# ECE477_schematic.net
KiCad netlist of a schematic drawn in EAGLE
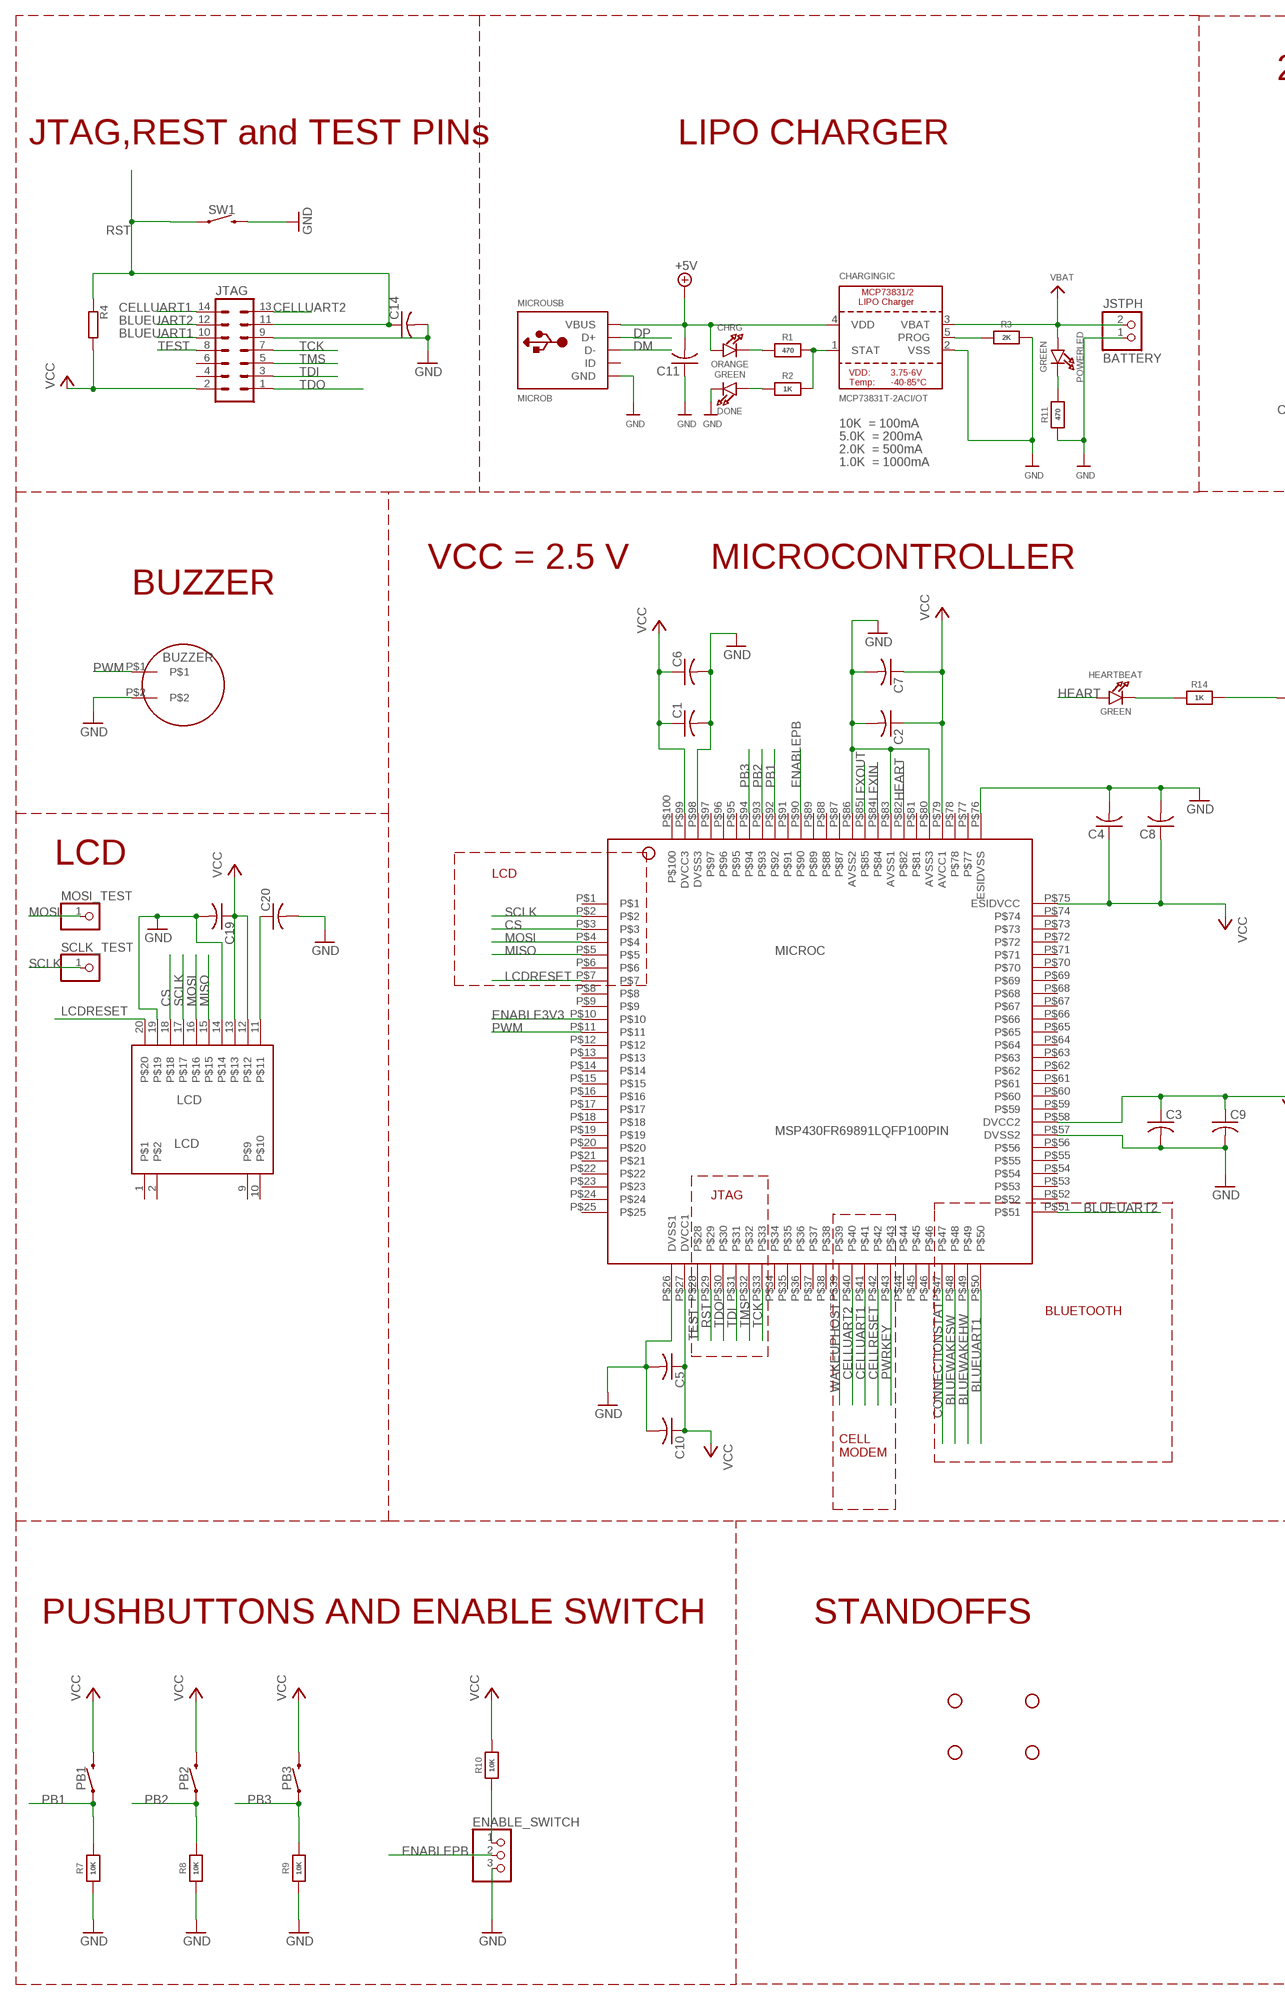
[diagram p0: schematic, sheet 1, part 1 of 2]
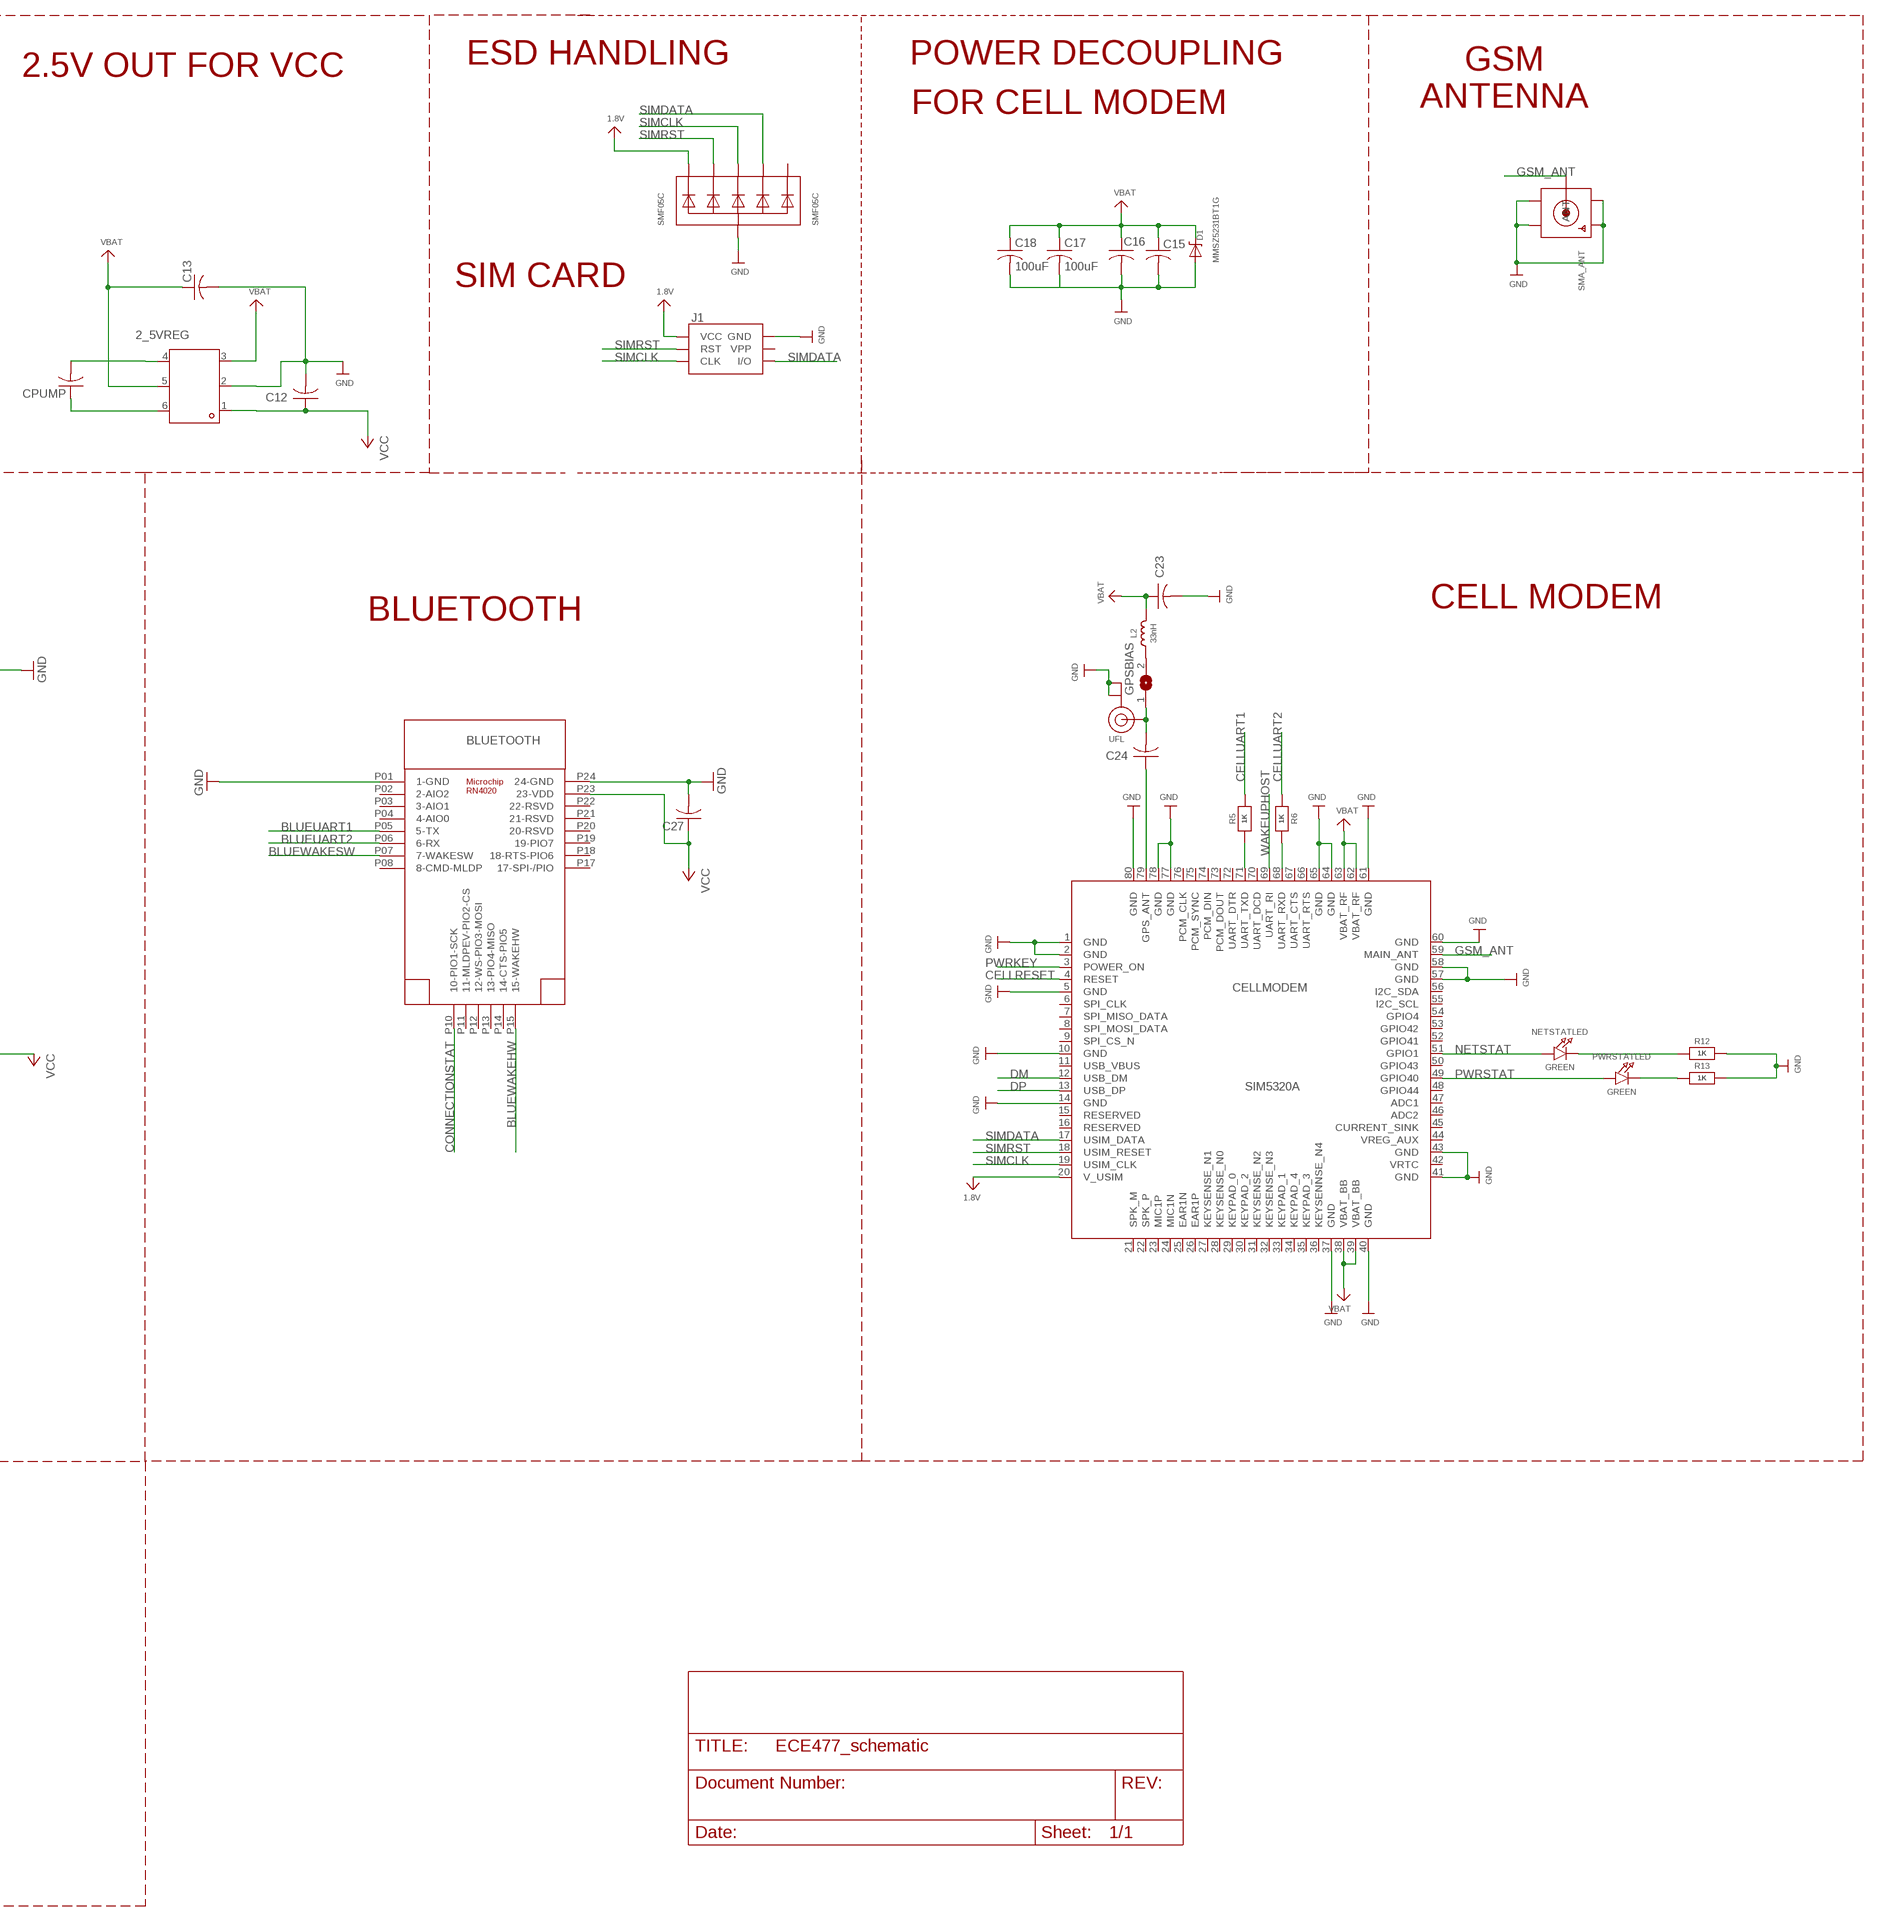
[diagram p1: schematic, sheet 1, part 2 of 2]

(export (version "E")
  (design (tool "Eeschema 10.0.6"))
  (components
    (comp (ref "2_5VREG")
      (value "2_5VREG")
      (footprint "eagle-import:REG710NASOC6")
      (libsource (lib "eagle-import") (part "2_5VREG"))
    )
    (comp (ref "BATTERY")
      (value "JSTPH")
      (footprint "eagle-import:JSTPH2")
      (libsource (lib "eagle-import") (part "JST_2PIN"))
    )
    (comp (ref "BLUETOOTH")
      (value "RN4020")
      (footprint "eagle-import:RN4020SMD")
      (libsource (lib "eagle-import") (part "RN4020"))
    )
    (comp (ref "BUZZER")
      (value "BUZZER")
      (footprint "eagle-import:BUZZERTHROUGHHOLE")
      (libsource (lib "eagle-import") (part "BUZZER"))
    )
    (comp (ref "C1")
      (value "C-USC1206")
      (footprint "eagle-import:C1206")
      (libsource (lib "eagle-import") (part "rcl_334_C-USC1206"))
    )
    (comp (ref "C2")
      (value "C-USC1206")
      (footprint "eagle-import:C1206")
      (libsource (lib "eagle-import") (part "rcl_334_C-USC1206"))
    )
    (comp (ref "C3")
      (value "C-USC1206")
      (footprint "eagle-import:C1206")
      (libsource (lib "eagle-import") (part "rcl_334_C-USC1206"))
    )
    (comp (ref "C4")
      (value "C-USC1206")
      (footprint "eagle-import:C1206")
      (libsource (lib "eagle-import") (part "rcl_334_C-USC1206"))
    )
    (comp (ref "C5")
      (value "C-USC1206")
      (footprint "eagle-import:C1206")
      (libsource (lib "eagle-import") (part "rcl_334_C-USC1206"))
    )
    (comp (ref "C6")
      (value "C-USC1206")
      (footprint "eagle-import:C1206")
      (libsource (lib "eagle-import") (part "rcl_334_C-USC1206"))
    )
    (comp (ref "C7")
      (value "C-USC1206")
      (footprint "eagle-import:C1206")
      (libsource (lib "eagle-import") (part "rcl_334_C-USC1206"))
    )
    (comp (ref "C8")
      (value "C-USC1206")
      (footprint "eagle-import:C1206")
      (libsource (lib "eagle-import") (part "rcl_334_C-USC1206"))
    )
    (comp (ref "C9")
      (value "C-USC1206")
      (footprint "eagle-import:C1206")
      (libsource (lib "eagle-import") (part "rcl_334_C-USC1206"))
    )
    (comp (ref "C10")
      (value "C-USC1206")
      (footprint "eagle-import:C1206")
      (libsource (lib "eagle-import") (part "rcl_334_C-USC1206"))
    )
    (comp (ref "C11")
      (value "C-USC1206")
      (footprint "eagle-import:C1206")
      (libsource (lib "eagle-import") (part "rcl_334_C-USC1206"))
    )
    (comp (ref "C12")
      (value "C-USC1206")
      (footprint "eagle-import:C1206")
      (libsource (lib "eagle-import") (part "rcl_334_C-USC1206"))
    )
    (comp (ref "C13")
      (value "C-USC1206")
      (footprint "eagle-import:C1206")
      (libsource (lib "eagle-import") (part "rcl_334_C-USC1206"))
    )
    (comp (ref "C14")
      (value "C-USC1206")
      (footprint "eagle-import:C1206")
      (libsource (lib "eagle-import") (part "rcl_334_C-USC1206"))
    )
    (comp (ref "C15")
      (value "C-USC1206")
      (footprint "eagle-import:C1206")
      (libsource (lib "eagle-import") (part "rcl_334_C-USC1206"))
    )
    (comp (ref "C16")
      (value "C-USC1206")
      (footprint "eagle-import:C1206")
      (libsource (lib "eagle-import") (part "rcl_334_C-USC1206"))
    )
    (comp (ref "C17")
      (value "100uF")
      (footprint "eagle-import:C1210")
      (libsource (lib "eagle-import") (part "C-USC1210"))
    )
    (comp (ref "C18")
      (value "100uF")
      (footprint "eagle-import:C1210")
      (libsource (lib "eagle-import") (part "C-USC1210"))
    )
    (comp (ref "C19")
      (value "C-USC1206")
      (footprint "eagle-import:C1206")
      (libsource (lib "eagle-import") (part "rcl_334_C-USC1206"))
    )
    (comp (ref "C20")
      (value "C-USC1206")
      (footprint "eagle-import:C1206")
      (libsource (lib "eagle-import") (part "rcl_334_C-USC1206"))
    )
    (comp (ref "C23")
      (value "C-USC1206")
      (footprint "eagle-import:C1206")
      (libsource (lib "eagle-import") (part "rcl_334_C-USC1206"))
    )
    (comp (ref "C24")
      (value "C-USC1206")
      (footprint "eagle-import:C1206")
      (libsource (lib "eagle-import") (part "rcl_334_C-USC1206"))
    )
    (comp (ref "C27")
      (value "C-USC1206")
      (footprint "eagle-import:C1206")
      (libsource (lib "eagle-import") (part "rcl_334_C-USC1206"))
    )
    (comp (ref "CELLMODEM")
      (value "SIM5320A")
      (footprint "eagle-import:MICROBUILDER_SIM5320")
      (libsource (lib "eagle-import") (part "SIM5320"))
    )
    (comp (ref "CHARGINGIC")
      (value "MCP73831T-2ACI/OT")
      (footprint "eagle-import:SOT23-5")
      (libsource (lib "eagle-import") (part "MCP73831/2"))
    )
    (comp (ref "CHRG")
      (value "ORANGE")
      (footprint "eagle-import:CHIPLED_0805_NOOUTLINE")
      (libsource (lib "eagle-import") (part "LED0805_NOOUTLINE"))
    )
    (comp (ref "CPUMP")
      (value "C-USC1206")
      (footprint "eagle-import:C1206")
      (libsource (lib "eagle-import") (part "rcl_334_C-USC1206"))
    )
    (comp (ref "D1")
      (value "MMSZ5231BT1G")
      (footprint "eagle-import:SOD-123")
      (libsource (lib "eagle-import") (part "DIODE-ZENERSOD123"))
    )
    (comp (ref "DONE")
      (value "GREEN")
      (footprint "eagle-import:CHIPLED_0805_NOOUTLINE")
      (libsource (lib "eagle-import") (part "LED0805_NOOUTLINE"))
    )
    (comp (ref "ENABLE_SWITCH")
      (value "PINHD-1X3")
      (footprint "eagle-import:1X03")
      (libsource (lib "eagle-import") (part "PINHD-1X3"))
    )
    (comp (ref "GPSBIAS")
      (value "SOLDERJUMPER")
      (footprint "eagle-import:SOLDERJUMPER_ARROW_NOPASTE")
      (libsource (lib "eagle-import") (part "SOLDERJUMPER"))
    )
    (comp (ref "H1")
      (value "STAND-OFF")
      (footprint "eagle-import:STAND-OFF")
      (libsource (lib "eagle-import") (part "STAND-OFF"))
    )
    (comp (ref "H2")
      (value "STAND-OFF")
      (footprint "eagle-import:STAND-OFF")
      (libsource (lib "eagle-import") (part "STAND-OFF"))
    )
    (comp (ref "H3")
      (value "STAND-OFF")
      (footprint "eagle-import:STAND-OFF")
      (libsource (lib "eagle-import") (part "STAND-OFF"))
    )
    (comp (ref "H4")
      (value "STAND-OFF")
      (footprint "eagle-import:STAND-OFF")
      (libsource (lib "eagle-import") (part "STAND-OFF"))
    )
    (comp (ref "HEARTBEAT")
      (value "GREEN")
      (footprint "eagle-import:CHIPLED_0805_NOOUTLINE")
      (libsource (lib "eagle-import") (part "LED0805_NOOUTLINE"))
    )
    (comp (ref "J1")
      (value "SIMHOLDERSIM")
      (footprint "eagle-import:SIMHOLDER")
      (libsource (lib "eagle-import") (part "SIMHOLDERSIM"))
    )
    (comp (ref "JTAG")
      (value "CON-ML_ML14")
      (footprint "eagle-import:CON-ML_ML14")
      (libsource (lib "eagle-import") (part "CON-ML_ML14"))
    )
    (comp (ref "L2")
      (value "33nH")
      (footprint "eagle-import:_0805MP")
      (libsource (lib "eagle-import") (part "INDUCTOR_0805MP"))
    )
    (comp (ref "LCD")
      (value "LCD")
      (footprint "eagle-import:LCDTHROUGHHOLE")
      (libsource (lib "eagle-import") (part "LCD"))
    )
    (comp (ref "MICROC")
      (value "MSP430FR69891LQFP100PIN")
      (footprint "eagle-import:MSP430FR69891")
      (libsource (lib "eagle-import") (part "MSP430FR69891LQFP100PIN"))
    )
    (comp (ref "MICROUSB")
      (value "MICROB")
      (footprint "eagle-import:ZX62DB5PA8(30)")
      (libsource (lib "eagle-import") (part "MICROB"))
    )
    (comp (ref "MOSI_TEST")
      (value "PINHD-1X1")
      (footprint "eagle-import:1X01")
      (libsource (lib "eagle-import") (part "PINHD-1X1"))
    )
    (comp (ref "NETSTATLED")
      (value "GREEN")
      (footprint "eagle-import:CHIPLED_0805_NOOUTLINE")
      (libsource (lib "eagle-import") (part "LED0805_NOOUTLINE"))
    )
    (comp (ref "PB1")
      (value "MOMENTARY-SWITCH-SPST-PTH-6.0MM")
      (footprint "eagle-import:TACTILE_SWITCH_PTH_6.0MM")
      (libsource (lib "eagle-import") (part "MOMENTARY-SWITCH-SPST-PTH-6.0MM"))
    )
    (comp (ref "PB2")
      (value "MOMENTARY-SWITCH-SPST-PTH-6.0MM")
      (footprint "eagle-import:TACTILE_SWITCH_PTH_6.0MM")
      (libsource (lib "eagle-import") (part "MOMENTARY-SWITCH-SPST-PTH-6.0MM"))
    )
    (comp (ref "PB3")
      (value "MOMENTARY-SWITCH-SPST-PTH-6.0MM")
      (footprint "eagle-import:TACTILE_SWITCH_PTH_6.0MM")
      (libsource (lib "eagle-import") (part "MOMENTARY-SWITCH-SPST-PTH-6.0MM"))
    )
    (comp (ref "POWERLED")
      (value "GREEN")
      (footprint "eagle-import:CHIPLED_0805_NOOUTLINE")
      (libsource (lib "eagle-import") (part "LED0805_NOOUTLINE"))
    )
    (comp (ref "PWRSTATLED")
      (value "GREEN")
      (footprint "eagle-import:CHIPLED_0805_NOOUTLINE")
      (libsource (lib "eagle-import") (part "LED0805_NOOUTLINE"))
    )
    (comp (ref "R1")
      (value "470")
      (footprint "eagle-import:0805-NO")
      (libsource (lib "eagle-import") (part "RESISTOR0805_NOOUTLINE"))
    )
    (comp (ref "R2")
      (value "1K")
      (footprint "eagle-import:0805-NO")
      (libsource (lib "eagle-import") (part "RESISTOR0805_NOOUTLINE"))
    )
    (comp (ref "R3")
      (value "2K")
      (footprint "eagle-import:0805-NO")
      (libsource (lib "eagle-import") (part "RESISTOR0805_NOOUTLINE"))
    )
    (comp (ref "R4")
      (value "SMD_R_0805")
      (footprint "eagle-import:SMD_0805")
      (libsource (lib "eagle-import") (part "SMD_R_0805"))
    )
    (comp (ref "R5")
      (value "1K")
      (footprint "eagle-import:0805-NO")
      (libsource (lib "eagle-import") (part "RESISTOR0805_NOOUTLINE"))
    )
    (comp (ref "R6")
      (value "1K")
      (footprint "eagle-import:0805-NO")
      (libsource (lib "eagle-import") (part "RESISTOR0805_NOOUTLINE"))
    )
    (comp (ref "R7")
      (value "10K")
      (footprint "eagle-import:0805-NO")
      (libsource (lib "eagle-import") (part "RESISTOR0805_NOOUTLINE"))
    )
    (comp (ref "R8")
      (value "10K")
      (footprint "eagle-import:0805-NO")
      (libsource (lib "eagle-import") (part "RESISTOR0805_NOOUTLINE"))
    )
    (comp (ref "R9")
      (value "10K")
      (footprint "eagle-import:0805-NO")
      (libsource (lib "eagle-import") (part "RESISTOR0805_NOOUTLINE"))
    )
    (comp (ref "R10")
      (value "10K")
      (footprint "eagle-import:0805-NO")
      (libsource (lib "eagle-import") (part "RESISTOR0805_NOOUTLINE"))
    )
    (comp (ref "R11")
      (value "470")
      (footprint "eagle-import:0805-NO")
      (libsource (lib "eagle-import") (part "RESISTOR0805_NOOUTLINE"))
    )
    (comp (ref "R12")
      (value "1K")
      (footprint "eagle-import:0805-NO")
      (libsource (lib "eagle-import") (part "RESISTOR0805_NOOUTLINE"))
    )
    (comp (ref "R13")
      (value "1K")
      (footprint "eagle-import:0805-NO")
      (libsource (lib "eagle-import") (part "RESISTOR0805_NOOUTLINE"))
    )
    (comp (ref "R14")
      (value "1K")
      (footprint "eagle-import:0805-NO")
      (libsource (lib "eagle-import") (part "RESISTOR0805_NOOUTLINE"))
    )
    (comp (ref "SCLK_TEST")
      (value "PINHD-1X1")
      (footprint "eagle-import:1X01")
      (libsource (lib "eagle-import") (part "PINHD-1X1"))
    )
    (comp (ref "SMA_ANT")
      (value "MICROBUILDER_SMACONNECTOR_EDGE")
      (footprint "eagle-import:MICROBUILDER_SMA_EDGELAUNCH")
      (libsource (lib "eagle-import") (part "MICROBUILDER_SMACONNECTOR_EDGE"))
    )
    (comp (ref "SMF05C")
      (value "SMF05C")
      (footprint "eagle-import:SOT363")
      (libsource (lib "eagle-import") (part "TVSARRAY_5LANE"))
    )
    (comp (ref "SW1")
      (value "MOMENTARY-SWITCH-SPST-PTH-6.0MM")
      (footprint "eagle-import:TACTILE_SWITCH_PTH_6.0MM")
      (libsource (lib "eagle-import") (part "MOMENTARY-SWITCH-SPST-PTH-6.0MM"))
    )
    (comp (ref "UFL")
      (value "MICROBUILDER_ANTENNA_U.FL")
      (footprint "eagle-import:MICROBUILDER_U.FL")
      (libsource (lib "eagle-import") (part "MICROBUILDER_ANTENNA_U.FL"))
    )
  )
  (nets
    (net (code "1") (name "+5V") (class "Default")
      (node (ref "C11") (pin "2") (pinfunction "2_2") (pintype "passive"))
      (node (ref "CHARGINGIC") (pin "4") (pinfunction "VDD_4") (pintype "power_in"))
      (node (ref "CHRG") (pin "A") (pinfunction "A_A") (pintype "passive"))
      (node (ref "MICROUSB") (pin "+5V") (pinfunction "VBUS_+5V") (pintype "power_in"))
    )
    (net (code "2") (name "/BLUEUART1") (class "Default")
      (node (ref "BLUETOOTH") (pin "P05") (pinfunction "5-TX_P05") (pintype "bidirectional"))
      (node (ref "JTAG") (pin "10") (pinfunction "10_10") (pintype "passive"))
      (node (ref "MICROC") (pin "P$50") (pinfunction "P$50_P$50") (pintype "bidirectional"))
    )
    (net (code "3") (name "/BLUEUART2") (class "Default")
      (node (ref "BLUETOOTH") (pin "P06") (pinfunction "6-RX_P06") (pintype "bidirectional"))
      (node (ref "JTAG") (pin "12") (pinfunction "12_12") (pintype "passive"))
      (node (ref "MICROC") (pin "P$51") (pinfunction "P$51_P$51") (pintype "bidirectional"))
    )
    (net (code "4") (name "/BLUEWAKEHW") (class "Default")
      (node (ref "BLUETOOTH") (pin "P15") (pinfunction "15-WAKEHW_P15") (pintype "bidirectional"))
      (node (ref "MICROC") (pin "P$49") (pinfunction "P$49_P$49") (pintype "bidirectional"))
    )
    (net (code "5") (name "/BLUEWAKESW") (class "Default")
      (node (ref "BLUETOOTH") (pin "P07") (pinfunction "7-WAKESW_P07") (pintype "bidirectional"))
      (node (ref "MICROC") (pin "P$48") (pinfunction "P$48_P$48") (pintype "bidirectional"))
    )
    (net (code "6") (name "/CELLRESET") (class "Default")
      (node (ref "CELLMODEM") (pin "4") (pinfunction "RESET_4") (pintype "bidirectional"))
      (node (ref "MICROC") (pin "P$42") (pinfunction "P$42_P$42") (pintype "bidirectional"))
    )
    (net (code "7") (name "/CELLUART1") (class "Default")
      (node (ref "JTAG") (pin "14") (pinfunction "14_14") (pintype "passive"))
      (node (ref "MICROC") (pin "P$41") (pinfunction "P$41_P$41") (pintype "bidirectional"))
      (node (ref "R5") (pin "2") (pinfunction "2_2") (pintype "passive"))
    )
    (net (code "8") (name "/CELLUART2") (class "Default")
      (node (ref "JTAG") (pin "13") (pinfunction "13_13") (pintype "passive"))
      (node (ref "MICROC") (pin "P$40") (pinfunction "P$40_P$40") (pintype "bidirectional"))
      (node (ref "R6") (pin "2") (pinfunction "2_2") (pintype "passive"))
    )
    (net (code "9") (name "/CONNECTIONSTAT") (class "Default")
      (node (ref "BLUETOOTH") (pin "P10") (pinfunction "10-PIO1-SCK_P10") (pintype "bidirectional"))
      (node (ref "MICROC") (pin "P$47") (pinfunction "P$47_P$47") (pintype "bidirectional"))
    )
    (net (code "10") (name "/CS") (class "Default")
      (node (ref "LCD") (pin "18") (pinfunction "P$18_18") (pintype "bidirectional"))
      (node (ref "MICROC") (pin "P$3") (pinfunction "P$3_P$3") (pintype "bidirectional"))
    )
    (net (code "11") (name "/DM") (class "Default")
      (node (ref "CELLMODEM") (pin "12") (pinfunction "USB_DM_12") (pintype "bidirectional"))
      (node (ref "MICROUSB") (pin "D-") (pinfunction "D-_D-") (pintype "bidirectional"))
    )
    (net (code "12") (name "/DP") (class "Default")
      (node (ref "CELLMODEM") (pin "13") (pinfunction "USB_DP_13") (pintype "bidirectional"))
      (node (ref "MICROUSB") (pin "D+") (pinfunction "D+_D+") (pintype "bidirectional"))
    )
    (net (code "13") (name "/ENABLE3V3") (class "Default")
      (node (ref "MICROC") (pin "P$10") (pinfunction "P$10_P$10") (pintype "bidirectional"))
    )
    (net (code "14") (name "/ENABLEPB") (class "Default")
      (node (ref "ENABLE_SWITCH") (pin "2") (pinfunction "2_2") (pintype "passive"))
      (node (ref "MICROC") (pin "P$90") (pinfunction "P$90_P$90") (pintype "bidirectional"))
    )
    (net (code "15") (name "/GSM_ANT") (class "Default")
      (node (ref "CELLMODEM") (pin "59") (pinfunction "MAIN_ANT_59") (pintype "bidirectional"))
      (node (ref "SMA_ANT") (pin "P") (pinfunction "ANT_P") (pintype "bidirectional"))
    )
    (net (code "16") (name "/HEART") (class "Default")
      (node (ref "HEARTBEAT") (pin "A") (pinfunction "A_A") (pintype "passive"))
      (node (ref "MICROC") (pin "P$82") (pinfunction "P$82_P$82") (pintype "bidirectional"))
    )
    (net (code "17") (name "/LCDRESET") (class "Default")
      (node (ref "LCD") (pin "20") (pinfunction "P$20_20") (pintype "bidirectional"))
      (node (ref "MICROC") (pin "P$7") (pinfunction "P$7_P$7") (pintype "bidirectional"))
    )
    (net (code "18") (name "/LFXIN") (class "Default")
      (node (ref "MICROC") (pin "P$84") (pinfunction "P$84_P$84") (pintype "bidirectional"))
    )
    (net (code "19") (name "/LFXOUT") (class "Default")
      (node (ref "MICROC") (pin "P$85") (pinfunction "P$85_P$85") (pintype "bidirectional"))
    )
    (net (code "20") (name "/MISO") (class "Default")
      (node (ref "LCD") (pin "15") (pinfunction "P$15_15") (pintype "bidirectional"))
      (node (ref "MICROC") (pin "P$5") (pinfunction "P$5_P$5") (pintype "bidirectional"))
    )
    (net (code "21") (name "/MOSI") (class "Default")
      (node (ref "LCD") (pin "16") (pinfunction "P$16_16") (pintype "bidirectional"))
      (node (ref "MICROC") (pin "P$4") (pinfunction "P$4_P$4") (pintype "bidirectional"))
      (node (ref "MOSI_TEST") (pin "1") (pinfunction "1_1") (pintype "passive"))
    )
    (net (code "22") (name "/NETSTAT") (class "Default")
      (node (ref "CELLMODEM") (pin "51") (pinfunction "GPIO1_51") (pintype "bidirectional"))
      (node (ref "NETSTATLED") (pin "A") (pinfunction "A_A") (pintype "passive"))
    )
    (net (code "23") (name "/PB1") (class "Default")
      (node (ref "MICROC") (pin "P$92") (pinfunction "P$92_P$92") (pintype "bidirectional"))
      (node (ref "PB1") (pin "1") (pinfunction "1_1") (pintype "passive"))
      (node (ref "R7") (pin "2") (pinfunction "2_2") (pintype "passive"))
    )
    (net (code "24") (name "/PB2") (class "Default")
      (node (ref "MICROC") (pin "P$93") (pinfunction "P$93_P$93") (pintype "bidirectional"))
      (node (ref "PB2") (pin "1") (pinfunction "1_1") (pintype "passive"))
      (node (ref "R8") (pin "2") (pinfunction "2_2") (pintype "passive"))
    )
    (net (code "25") (name "/PB3") (class "Default")
      (node (ref "MICROC") (pin "P$94") (pinfunction "P$94_P$94") (pintype "bidirectional"))
      (node (ref "PB3") (pin "1") (pinfunction "1_1") (pintype "passive"))
      (node (ref "R9") (pin "2") (pinfunction "2_2") (pintype "passive"))
    )
    (net (code "26") (name "/PWM") (class "Default")
      (node (ref "BUZZER") (pin "P$1") (pinfunction "P$1_P$1") (pintype "bidirectional"))
      (node (ref "MICROC") (pin "P$11") (pinfunction "P$11_P$11") (pintype "bidirectional"))
    )
    (net (code "27") (name "/PWRKEY") (class "Default")
      (node (ref "CELLMODEM") (pin "3") (pinfunction "POWER_ON_3") (pintype "bidirectional"))
      (node (ref "MICROC") (pin "P$43") (pinfunction "P$43_P$43") (pintype "bidirectional"))
    )
    (net (code "28") (name "/PWRSTAT") (class "Default")
      (node (ref "CELLMODEM") (pin "49") (pinfunction "GPIO40_49") (pintype "bidirectional"))
      (node (ref "PWRSTATLED") (pin "A") (pinfunction "A_A") (pintype "passive"))
    )
    (net (code "29") (name "/RST") (class "Default")
      (node (ref "C14") (pin "1") (pinfunction "1_1") (pintype "passive"))
      (node (ref "JTAG") (pin "11") (pinfunction "11_11") (pintype "passive"))
      (node (ref "MICROC") (pin "P$29") (pinfunction "P$29_P$29") (pintype "bidirectional"))
      (node (ref "R4") (pin "1") (pinfunction "1_1") (pintype "passive"))
      (node (ref "SW1") (pin "1") (pinfunction "1_1") (pintype "passive"))
    )
    (net (code "30") (name "/SCLK") (class "Default")
      (node (ref "LCD") (pin "17") (pinfunction "P$17_17") (pintype "bidirectional"))
      (node (ref "MICROC") (pin "P$2") (pinfunction "P$2_P$2") (pintype "bidirectional"))
      (node (ref "SCLK_TEST") (pin "1") (pinfunction "1_1") (pintype "passive"))
    )
    (net (code "31") (name "/SIMCLK") (class "Default")
      (node (ref "CELLMODEM") (pin "19") (pinfunction "USIM_CLK_19") (pintype "bidirectional"))
      (node (ref "J1") (pin "C3") (pinfunction "CLK_C3") (pintype "input"))
      (node (ref "SMF05C") (pin "4") (pinfunction "C3_4") (pintype "passive"))
    )
    (net (code "32") (name "/SIMDATA") (class "Default")
      (node (ref "CELLMODEM") (pin "17") (pinfunction "USIM_DATA_17") (pintype "bidirectional"))
      (node (ref "J1") (pin "C7") (pinfunction "I/O_C7") (pintype "bidirectional"))
      (node (ref "SMF05C") (pin "5") (pinfunction "C4_5") (pintype "passive"))
    )
    (net (code "33") (name "/SIMRST") (class "Default")
      (node (ref "CELLMODEM") (pin "18") (pinfunction "USIM_RESET_18") (pintype "bidirectional"))
      (node (ref "J1") (pin "C2") (pinfunction "RST_C2") (pintype "input"))
      (node (ref "SMF05C") (pin "3") (pinfunction "C2_3") (pintype "passive"))
    )
    (net (code "34") (name "/TCK") (class "Default")
      (node (ref "JTAG") (pin "7") (pinfunction "7_7") (pintype "passive"))
      (node (ref "MICROC") (pin "P$33") (pinfunction "P$33_P$33") (pintype "bidirectional"))
    )
    (net (code "35") (name "/TDI") (class "Default")
      (node (ref "JTAG") (pin "3") (pinfunction "3_3") (pintype "passive"))
      (node (ref "MICROC") (pin "P$31") (pinfunction "P$31_P$31") (pintype "bidirectional"))
    )
    (net (code "36") (name "/TDO") (class "Default")
      (node (ref "JTAG") (pin "1") (pinfunction "1_1") (pintype "passive"))
      (node (ref "MICROC") (pin "P$30") (pinfunction "P$30_P$30") (pintype "bidirectional"))
    )
    (net (code "37") (name "/TEST") (class "Default")
      (node (ref "JTAG") (pin "8") (pinfunction "8_8") (pintype "passive"))
      (node (ref "MICROC") (pin "P$28") (pinfunction "P$28_P$28") (pintype "bidirectional"))
    )
    (net (code "38") (name "/TMS") (class "Default")
      (node (ref "JTAG") (pin "5") (pinfunction "5_5") (pintype "passive"))
      (node (ref "MICROC") (pin "P$32") (pinfunction "P$32_P$32") (pintype "bidirectional"))
    )
    (net (code "39") (name "/WAKEUPHOST") (class "Default")
      (node (ref "CELLMODEM") (pin "69") (pinfunction "UART_RI_69") (pintype "bidirectional"))
      (node (ref "MICROC") (pin "P$39") (pinfunction "P$39_P$39") (pintype "bidirectional"))
    )
    (net (code "40") (name "1.8V") (class "Default")
      (node (ref "CELLMODEM") (pin "20") (pinfunction "V_USIM_20") (pintype "bidirectional"))
      (node (ref "J1") (pin "C1") (pinfunction "VCC_C1") (pintype "power_in"))
      (node (ref "SMF05C") (pin "1") (pinfunction "C1_1") (pintype "passive"))
    )
    (net (code "41") (name "GND") (class "Default")
      (node (ref "2_5VREG") (pin "2") (pinfunction "2_2") (pintype "bidirectional"))
      (node (ref "BATTERY") (pin "1") (pinfunction "1_1") (pintype "passive"))
      (node (ref "BLUETOOTH") (pin "P01") (pinfunction "1-GND_P01") (pintype "bidirectional"))
      (node (ref "BLUETOOTH") (pin "P24") (pinfunction "24-GND_P24") (pintype "bidirectional"))
      (node (ref "BUZZER") (pin "P$2") (pinfunction "P$2_P$2") (pintype "bidirectional"))
      (node (ref "C1") (pin "2") (pinfunction "2_2") (pintype "passive"))
      (node (ref "C10") (pin "2") (pinfunction "2_2") (pintype "passive"))
      (node (ref "C11") (pin "1") (pinfunction "1_1") (pintype "passive"))
      (node (ref "C12") (pin "2") (pinfunction "2_2") (pintype "passive"))
      (node (ref "C13") (pin "2") (pinfunction "2_2") (pintype "passive"))
      (node (ref "C14") (pin "2") (pinfunction "2_2") (pintype "passive"))
      (node (ref "C15") (pin "2") (pinfunction "2_2") (pintype "passive"))
      (node (ref "C16") (pin "2") (pinfunction "2_2") (pintype "passive"))
      (node (ref "C17") (pin "2") (pinfunction "2_2") (pintype "passive"))
      (node (ref "C18") (pin "2") (pinfunction "2_2") (pintype "passive"))
      (node (ref "C19") (pin "2") (pinfunction "2_2") (pintype "passive"))
      (node (ref "C2") (pin "2") (pinfunction "2_2") (pintype "passive"))
      (node (ref "C20") (pin "2") (pinfunction "2_2") (pintype "passive"))
      (node (ref "C23") (pin "2") (pinfunction "2_2") (pintype "passive"))
      (node (ref "C27") (pin "2") (pinfunction "2_2") (pintype "passive"))
      (node (ref "C3") (pin "2") (pinfunction "2_2") (pintype "passive"))
      (node (ref "C4") (pin "2") (pinfunction "2_2") (pintype "passive"))
      (node (ref "C5") (pin "2") (pinfunction "2_2") (pintype "passive"))
      (node (ref "C6") (pin "2") (pinfunction "2_2") (pintype "passive"))
      (node (ref "C7") (pin "2") (pinfunction "2_2") (pintype "passive"))
      (node (ref "C8") (pin "2") (pinfunction "2_2") (pintype "passive"))
      (node (ref "C9") (pin "2") (pinfunction "2_2") (pintype "passive"))
      (node (ref "CELLMODEM") (pin "1") (pinfunction "GND_1") (pintype "bidirectional"))
      (node (ref "CELLMODEM") (pin "10") (pinfunction "GND_10") (pintype "bidirectional"))
      (node (ref "CELLMODEM") (pin "14") (pinfunction "GND_14") (pintype "bidirectional"))
      (node (ref "CELLMODEM") (pin "2") (pinfunction "GND_2") (pintype "bidirectional"))
      (node (ref "CELLMODEM") (pin "37") (pinfunction "GND_37") (pintype "bidirectional"))
      (node (ref "CELLMODEM") (pin "40") (pinfunction "GND_40") (pintype "bidirectional"))
      (node (ref "CELLMODEM") (pin "41") (pinfunction "GND_41") (pintype "bidirectional"))
      (node (ref "CELLMODEM") (pin "43") (pinfunction "GND_43") (pintype "bidirectional"))
      (node (ref "CELLMODEM") (pin "5") (pinfunction "GND_5") (pintype "bidirectional"))
      (node (ref "CELLMODEM") (pin "57") (pinfunction "GND_57") (pintype "bidirectional"))
      (node (ref "CELLMODEM") (pin "58") (pinfunction "GND_58") (pintype "bidirectional"))
      (node (ref "CELLMODEM") (pin "60") (pinfunction "GND_60") (pintype "bidirectional"))
      (node (ref "CELLMODEM") (pin "61") (pinfunction "GND_61") (pintype "bidirectional"))
      (node (ref "CELLMODEM") (pin "64") (pinfunction "GND_64") (pintype "bidirectional"))
      (node (ref "CELLMODEM") (pin "65") (pinfunction "GND_65") (pintype "bidirectional"))
      (node (ref "CELLMODEM") (pin "77") (pinfunction "GND_77") (pintype "bidirectional"))
      (node (ref "CELLMODEM") (pin "78") (pinfunction "GND_78") (pintype "bidirectional"))
      (node (ref "CELLMODEM") (pin "80") (pinfunction "GND_80") (pintype "bidirectional"))
      (node (ref "CHARGINGIC") (pin "2") (pinfunction "VSS_2") (pintype "power_in"))
      (node (ref "D1") (pin "A") (pinfunction "A_A") (pintype "passive"))
      (node (ref "DONE") (pin "C") (pinfunction "C_C") (pintype "passive"))
      (node (ref "ENABLE_SWITCH") (pin "3") (pinfunction "3_3") (pintype "passive"))
      (node (ref "J1") (pin "C5") (pinfunction "GND_C5") (pintype "power_in"))
      (node (ref "JTAG") (pin "9") (pinfunction "9_9") (pintype "passive"))
      (node (ref "LCD") (pin "14") (pinfunction "P$14_14") (pintype "bidirectional"))
      (node (ref "LCD") (pin "19") (pinfunction "P$19_19") (pintype "bidirectional"))
      (node (ref "MICROC") (pin "P$26") (pinfunction "DVSS1_P$26") (pintype "bidirectional"))
      (node (ref "MICROC") (pin "P$57") (pinfunction "DVSS2_P$57") (pintype "bidirectional"))
      (node (ref "MICROC") (pin "P$76") (pinfunction "ESIDVSS_P$76") (pintype "bidirectional"))
      (node (ref "MICROC") (pin "P$80") (pinfunction "AVSS3_P$80") (pintype "bidirectional"))
      (node (ref "MICROC") (pin "P$83") (pinfunction "AVSS1_P$83") (pintype "bidirectional"))
      (node (ref "MICROC") (pin "P$86") (pinfunction "AVSS2_P$86") (pintype "bidirectional"))
      (node (ref "MICROC") (pin "P$98") (pinfunction "DVSS3_P$98") (pintype "bidirectional"))
      (node (ref "MICROUSB") (pin "GND") (pinfunction "GND_GND") (pintype "power_in"))
      (node (ref "R11") (pin "1") (pinfunction "1_1") (pintype "passive"))
      (node (ref "R12") (pin "2") (pinfunction "2_2") (pintype "passive"))
      (node (ref "R13") (pin "2") (pinfunction "2_2") (pintype "passive"))
      (node (ref "R14") (pin "2") (pinfunction "2_2") (pintype "passive"))
      (node (ref "R3") (pin "2") (pinfunction "2_2") (pintype "passive"))
      (node (ref "R7") (pin "1") (pinfunction "1_1") (pintype "passive"))
      (node (ref "R8") (pin "1") (pinfunction "1_1") (pintype "passive"))
      (node (ref "R9") (pin "1") (pinfunction "1_1") (pintype "passive"))
      (node (ref "SMA_ANT") (pin "GND@1") (pinfunction "GND4_GND@1") (pintype "power_in"))
      (node (ref "SMA_ANT") (pin "GND@2") (pinfunction "GND3_GND@2") (pintype "power_in"))
      (node (ref "SMA_ANT") (pin "GND@3") (pinfunction "GND2_GND@3") (pintype "power_in"))
      (node (ref "SMA_ANT") (pin "GND@4") (pinfunction "GND1_GND@4") (pintype "power_in"))
      (node (ref "SMF05C") (pin "2") (pinfunction "A_2") (pintype "passive"))
      (node (ref "SW1") (pin "3") (pinfunction "2_3") (pintype "passive"))
      (node (ref "UFL") (pin "1") (pinfunction "GND_1") (pintype "passive"))
      (node (ref "UFL") (pin "2") (pinfunction "GND_2") (pintype "passive"))
    )
    (net (code "42") (name "Net-(2_5VREG-Pad4)") (class "Default")
      (node (ref "2_5VREG") (pin "4") (pinfunction "4_4") (pintype "bidirectional"))
      (node (ref "CPUMP") (pin "2") (pinfunction "2_2") (pintype "passive"))
    )
    (net (code "43") (name "Net-(2_5VREG-Pad6)") (class "Default")
      (node (ref "2_5VREG") (pin "6") (pinfunction "6_6") (pintype "bidirectional"))
      (node (ref "CPUMP") (pin "1") (pinfunction "1_1") (pintype "passive"))
    )
    (net (code "44") (name "Net-(CELLMODEM-GPS_ANT)") (class "Default")
      (node (ref "C24") (pin "1") (pinfunction "1_1") (pintype "passive"))
      (node (ref "CELLMODEM") (pin "79") (pinfunction "GPS_ANT_79") (pintype "bidirectional"))
    )
    (net (code "45") (name "Net-(CELLMODEM-UART_RXD)") (class "Default")
      (node (ref "CELLMODEM") (pin "68") (pinfunction "UART_RXD_68") (pintype "bidirectional"))
      (node (ref "R6") (pin "1") (pinfunction "1_1") (pintype "passive"))
    )
    (net (code "46") (name "Net-(CELLMODEM-UART_TXD)") (class "Default")
      (node (ref "CELLMODEM") (pin "71") (pinfunction "UART_TXD_71") (pintype "bidirectional"))
      (node (ref "R5") (pin "1") (pinfunction "1_1") (pintype "passive"))
    )
    (net (code "47") (name "Net-(CHARGINGIC-PROG)") (class "Default")
      (node (ref "CHARGINGIC") (pin "5") (pinfunction "PROG_5") (pintype "input"))
      (node (ref "R3") (pin "1") (pinfunction "1_1") (pintype "passive"))
    )
    (net (code "48") (name "Net-(CHARGINGIC-STAT)") (class "Default")
      (node (ref "CHARGINGIC") (pin "1") (pinfunction "STAT_1") (pintype "output"))
      (node (ref "R1") (pin "2") (pinfunction "2_2") (pintype "passive"))
      (node (ref "R2") (pin "2") (pinfunction "2_2") (pintype "passive"))
    )
    (net (code "49") (name "Net-(CHRG-PadC)") (class "Default")
      (node (ref "CHRG") (pin "C") (pinfunction "C_C") (pintype "passive"))
      (node (ref "R1") (pin "1") (pinfunction "1_1") (pintype "passive"))
    )
    (net (code "50") (name "Net-(DONE-PadA)") (class "Default")
      (node (ref "DONE") (pin "A") (pinfunction "A_A") (pintype "passive"))
      (node (ref "R2") (pin "1") (pinfunction "1_1") (pintype "passive"))
    )
    (net (code "51") (name "Net-(ENABLE_SWITCH-Pad1)") (class "Default")
      (node (ref "ENABLE_SWITCH") (pin "1") (pinfunction "1_1") (pintype "passive"))
      (node (ref "R10") (pin "1") (pinfunction "1_1") (pintype "passive"))
    )
    (net (code "52") (name "Net-(GPSBIAS-Pad2)") (class "Default")
      (node (ref "GPSBIAS") (pin "2") (pinfunction "2_2") (pintype "passive"))
      (node (ref "L2") (pin "1") (pinfunction "1_1") (pintype "passive"))
    )
    (net (code "53") (name "Net-(HEARTBEAT-PadC)") (class "Default")
      (node (ref "HEARTBEAT") (pin "C") (pinfunction "C_C") (pintype "passive"))
      (node (ref "R14") (pin "1") (pinfunction "1_1") (pintype "passive"))
    )
    (net (code "54") (name "Net-(LCD-P$11)") (class "Default")
      (node (ref "C20") (pin "1") (pinfunction "1_1") (pintype "passive"))
      (node (ref "LCD") (pin "11") (pinfunction "P$11_11") (pintype "bidirectional"))
    )
    (net (code "55") (name "Net-(NETSTATLED-PadC)") (class "Default")
      (node (ref "NETSTATLED") (pin "C") (pinfunction "C_C") (pintype "passive"))
      (node (ref "R12") (pin "1") (pinfunction "1_1") (pintype "passive"))
    )
    (net (code "56") (name "Net-(POWERLED-PadC)") (class "Default")
      (node (ref "POWERLED") (pin "C") (pinfunction "C_C") (pintype "passive"))
      (node (ref "R11") (pin "2") (pinfunction "2_2") (pintype "passive"))
    )
    (net (code "57") (name "Net-(PWRSTATLED-PadC)") (class "Default")
      (node (ref "PWRSTATLED") (pin "C") (pinfunction "C_C") (pintype "passive"))
      (node (ref "R13") (pin "1") (pinfunction "1_1") (pintype "passive"))
    )
    (net (code "58") (name "Net-(UFL-SIGNAL)") (class "Default")
      (node (ref "C24") (pin "2") (pinfunction "2_2") (pintype "passive"))
      (node (ref "GPSBIAS") (pin "1") (pinfunction "1_1") (pintype "passive"))
      (node (ref "UFL") (pin "3") (pinfunction "SIGNAL_3") (pintype "passive"))
    )
    (net (code "59") (name "VBAT") (class "Default")
      (node (ref "2_5VREG") (pin "3") (pinfunction "3_3") (pintype "bidirectional"))
      (node (ref "2_5VREG") (pin "5") (pinfunction "5_5") (pintype "bidirectional"))
      (node (ref "BATTERY") (pin "2") (pinfunction "2_2") (pintype "passive"))
      (node (ref "C13") (pin "1") (pinfunction "1_1") (pintype "passive"))
      (node (ref "C15") (pin "1") (pinfunction "1_1") (pintype "passive"))
      (node (ref "C16") (pin "1") (pinfunction "1_1") (pintype "passive"))
      (node (ref "C17") (pin "1") (pinfunction "1_1") (pintype "passive"))
      (node (ref "C18") (pin "1") (pinfunction "1_1") (pintype "passive"))
      (node (ref "C23") (pin "1") (pinfunction "1_1") (pintype "passive"))
      (node (ref "CELLMODEM") (pin "38") (pinfunction "VBAT_BB_38") (pintype "bidirectional"))
      (node (ref "CELLMODEM") (pin "39") (pinfunction "VBAT_BB_39") (pintype "bidirectional"))
      (node (ref "CELLMODEM") (pin "62") (pinfunction "VBAT_RF_62") (pintype "bidirectional"))
      (node (ref "CELLMODEM") (pin "63") (pinfunction "VBAT_RF_63") (pintype "bidirectional"))
      (node (ref "CHARGINGIC") (pin "3") (pinfunction "VBAT_3") (pintype "power_in"))
      (node (ref "D1") (pin "C") (pinfunction "C_C") (pintype "passive"))
      (node (ref "L2") (pin "2") (pinfunction "2_2") (pintype "passive"))
      (node (ref "POWERLED") (pin "A") (pinfunction "A_A") (pintype "passive"))
    )
    (net (code "60") (name "VCC") (class "Default")
      (node (ref "2_5VREG") (pin "1") (pinfunction "1_1") (pintype "bidirectional"))
      (node (ref "BLUETOOTH") (pin "P23") (pinfunction "23-VDD_P23") (pintype "bidirectional"))
      (node (ref "C1") (pin "1") (pinfunction "1_1") (pintype "passive"))
      (node (ref "C10") (pin "1") (pinfunction "1_1") (pintype "passive"))
      (node (ref "C12") (pin "1") (pinfunction "1_1") (pintype "passive"))
      (node (ref "C19") (pin "1") (pinfunction "1_1") (pintype "passive"))
      (node (ref "C2") (pin "1") (pinfunction "1_1") (pintype "passive"))
      (node (ref "C27") (pin "1") (pinfunction "1_1") (pintype "passive"))
      (node (ref "C3") (pin "1") (pinfunction "1_1") (pintype "passive"))
      (node (ref "C4") (pin "1") (pinfunction "1_1") (pintype "passive"))
      (node (ref "C5") (pin "1") (pinfunction "1_1") (pintype "passive"))
      (node (ref "C6") (pin "1") (pinfunction "1_1") (pintype "passive"))
      (node (ref "C7") (pin "1") (pinfunction "1_1") (pintype "passive"))
      (node (ref "C8") (pin "1") (pinfunction "1_1") (pintype "passive"))
      (node (ref "C9") (pin "1") (pinfunction "1_1") (pintype "passive"))
      (node (ref "JTAG") (pin "2") (pinfunction "2_2") (pintype "passive"))
      (node (ref "LCD") (pin "12") (pinfunction "P$12_12") (pintype "bidirectional"))
      (node (ref "LCD") (pin "13") (pinfunction "P$13_13") (pintype "bidirectional"))
      (node (ref "MICROC") (pin "P$27") (pinfunction "DVCC1_P$27") (pintype "bidirectional"))
      (node (ref "MICROC") (pin "P$58") (pinfunction "DVCC2_P$58") (pintype "bidirectional"))
      (node (ref "MICROC") (pin "P$75") (pinfunction "ESIDVCC_P$75") (pintype "bidirectional"))
      (node (ref "MICROC") (pin "P$79") (pinfunction "AVCC1_P$79") (pintype "bidirectional"))
      (node (ref "MICROC") (pin "P$99") (pinfunction "DVCC3_P$99") (pintype "bidirectional"))
      (node (ref "PB1") (pin "3") (pinfunction "2_3") (pintype "passive"))
      (node (ref "PB2") (pin "3") (pinfunction "2_3") (pintype "passive"))
      (node (ref "PB3") (pin "3") (pinfunction "2_3") (pintype "passive"))
      (node (ref "R10") (pin "2") (pinfunction "2_2") (pintype "passive"))
      (node (ref "R4") (pin "2") (pinfunction "2_2") (pintype "passive"))
    )
    (net (code "61") (name "unconnected-(BLUETOOTH-2-AIO2-PadP02)") (class "Default")
      (node (ref "BLUETOOTH") (pin "P02") (pinfunction "2-AIO2_P02") (pintype "bidirectional"))
    )
    (net (code "62") (name "unconnected-(BLUETOOTH-3-AIO1-PadP03)") (class "Default")
      (node (ref "BLUETOOTH") (pin "P03") (pinfunction "3-AIO1_P03") (pintype "bidirectional"))
    )
    (net (code "63") (name "unconnected-(BLUETOOTH-4-AIO0-PadP04)") (class "Default")
      (node (ref "BLUETOOTH") (pin "P04") (pinfunction "4-AIO0_P04") (pintype "bidirectional"))
    )
    (net (code "64") (name "unconnected-(BLUETOOTH-8-CMD-MLDP-PadP08)") (class "Default")
      (node (ref "BLUETOOTH") (pin "P08") (pinfunction "8-CMD-MLDP_P08") (pintype "bidirectional"))
    )
    (net (code "65") (name "unconnected-(BLUETOOTH-11-MLDPEV-PIO2-CS-PadP11)") (class "Default")
      (node (ref "BLUETOOTH") (pin "P11") (pinfunction "11-MLDPEV-PIO2-CS_P11") (pintype "bidirectional"))
    )
    (net (code "66") (name "unconnected-(BLUETOOTH-12-WS-PIO3-MOSI-PadP12)") (class "Default")
      (node (ref "BLUETOOTH") (pin "P12") (pinfunction "12-WS-PIO3-MOSI_P12") (pintype "bidirectional"))
    )
    (net (code "67") (name "unconnected-(BLUETOOTH-13-PIO4-MISO-PadP13)") (class "Default")
      (node (ref "BLUETOOTH") (pin "P13") (pinfunction "13-PIO4-MISO_P13") (pintype "bidirectional"))
    )
    (net (code "68") (name "unconnected-(BLUETOOTH-14-CTS-PIO5-PadP14)") (class "Default")
      (node (ref "BLUETOOTH") (pin "P14") (pinfunction "14-CTS-PIO5_P14") (pintype "bidirectional"))
    )
    (net (code "69") (name "unconnected-(BLUETOOTH-17-SPI-{slash}PIO-PadP17)") (class "Default")
      (node (ref "BLUETOOTH") (pin "P17") (pinfunction "17-SPI-/PIO_P17") (pintype "bidirectional"))
    )
    (net (code "70") (name "unconnected-(BLUETOOTH-18-RTS-PIO6-PadP18)") (class "Default")
      (node (ref "BLUETOOTH") (pin "P18") (pinfunction "18-RTS-PIO6_P18") (pintype "bidirectional"))
    )
    (net (code "71") (name "unconnected-(BLUETOOTH-19-PIO7-PadP19)") (class "Default")
      (node (ref "BLUETOOTH") (pin "P19") (pinfunction "19-PIO7_P19") (pintype "bidirectional"))
    )
    (net (code "72") (name "unconnected-(BLUETOOTH-20-RSVD-PadP20)") (class "Default")
      (node (ref "BLUETOOTH") (pin "P20") (pinfunction "20-RSVD_P20") (pintype "bidirectional"))
    )
    (net (code "73") (name "unconnected-(BLUETOOTH-21-RSVD-PadP21)") (class "Default")
      (node (ref "BLUETOOTH") (pin "P21") (pinfunction "21-RSVD_P21") (pintype "bidirectional"))
    )
    (net (code "74") (name "unconnected-(BLUETOOTH-22-RSVD-PadP22)") (class "Default")
      (node (ref "BLUETOOTH") (pin "P22") (pinfunction "22-RSVD_P22") (pintype "bidirectional"))
    )
    (net (code "75") (name "unconnected-(CELLMODEM-ADC1-Pad47)") (class "Default")
      (node (ref "CELLMODEM") (pin "47") (pinfunction "ADC1_47") (pintype "bidirectional"))
    )
    (net (code "76") (name "unconnected-(CELLMODEM-ADC2-Pad46)") (class "Default")
      (node (ref "CELLMODEM") (pin "46") (pinfunction "ADC2_46") (pintype "bidirectional"))
    )
    (net (code "77") (name "unconnected-(CELLMODEM-CURRENT_SINK-Pad45)") (class "Default")
      (node (ref "CELLMODEM") (pin "45") (pinfunction "CURRENT_SINK_45") (pintype "bidirectional"))
    )
    (net (code "78") (name "unconnected-(CELLMODEM-EAR1N-Pad25)") (class "Default")
      (node (ref "CELLMODEM") (pin "25") (pinfunction "EAR1N_25") (pintype "bidirectional"))
    )
    (net (code "79") (name "unconnected-(CELLMODEM-EAR1P-Pad26)") (class "Default")
      (node (ref "CELLMODEM") (pin "26") (pinfunction "EAR1P_26") (pintype "bidirectional"))
    )
    (net (code "80") (name "unconnected-(CELLMODEM-GPIO4-Pad54)") (class "Default")
      (node (ref "CELLMODEM") (pin "54") (pinfunction "GPIO4_54") (pintype "bidirectional"))
    )
    (net (code "81") (name "unconnected-(CELLMODEM-GPIO41-Pad52)") (class "Default")
      (node (ref "CELLMODEM") (pin "52") (pinfunction "GPIO41_52") (pintype "bidirectional"))
    )
    (net (code "82") (name "unconnected-(CELLMODEM-GPIO42-Pad53)") (class "Default")
      (node (ref "CELLMODEM") (pin "53") (pinfunction "GPIO42_53") (pintype "bidirectional"))
    )
    (net (code "83") (name "unconnected-(CELLMODEM-GPIO43-Pad50)") (class "Default")
      (node (ref "CELLMODEM") (pin "50") (pinfunction "GPIO43_50") (pintype "bidirectional"))
    )
    (net (code "84") (name "unconnected-(CELLMODEM-GPIO44-Pad48)") (class "Default")
      (node (ref "CELLMODEM") (pin "48") (pinfunction "GPIO44_48") (pintype "bidirectional"))
    )
    (net (code "85") (name "unconnected-(CELLMODEM-I2C_SCL-Pad55)") (class "Default")
      (node (ref "CELLMODEM") (pin "55") (pinfunction "I2C_SCL_55") (pintype "bidirectional"))
    )
    (net (code "86") (name "unconnected-(CELLMODEM-I2C_SDA-Pad56)") (class "Default")
      (node (ref "CELLMODEM") (pin "56") (pinfunction "I2C_SDA_56") (pintype "bidirectional"))
    )
    (net (code "87") (name "unconnected-(CELLMODEM-KEYPAD_0-Pad29)") (class "Default")
      (node (ref "CELLMODEM") (pin "29") (pinfunction "KEYPAD_0_29") (pintype "bidirectional"))
    )
    (net (code "88") (name "unconnected-(CELLMODEM-KEYPAD_1-Pad33)") (class "Default")
      (node (ref "CELLMODEM") (pin "33") (pinfunction "KEYPAD_1_33") (pintype "bidirectional"))
    )
    (net (code "89") (name "unconnected-(CELLMODEM-KEYPAD_2-Pad30)") (class "Default")
      (node (ref "CELLMODEM") (pin "30") (pinfunction "KEYPAD_2_30") (pintype "bidirectional"))
    )
    (net (code "90") (name "unconnected-(CELLMODEM-KEYPAD_3-Pad35)") (class "Default")
      (node (ref "CELLMODEM") (pin "35") (pinfunction "KEYPAD_3_35") (pintype "bidirectional"))
    )
    (net (code "91") (name "unconnected-(CELLMODEM-KEYPAD_4-Pad34)") (class "Default")
      (node (ref "CELLMODEM") (pin "34") (pinfunction "KEYPAD_4_34") (pintype "bidirectional"))
    )
    (net (code "92") (name "unconnected-(CELLMODEM-KEYSENNSE_N4-Pad36)") (class "Default")
      (node (ref "CELLMODEM") (pin "36") (pinfunction "KEYSENNSE_N4_36") (pintype "bidirectional"))
    )
    (net (code "93") (name "unconnected-(CELLMODEM-KEYSENSE_N0-Pad28)") (class "Default")
      (node (ref "CELLMODEM") (pin "28") (pinfunction "KEYSENSE_N0_28") (pintype "bidirectional"))
    )
    (net (code "94") (name "unconnected-(CELLMODEM-KEYSENSE_N1-Pad27)") (class "Default")
      (node (ref "CELLMODEM") (pin "27") (pinfunction "KEYSENSE_N1_27") (pintype "bidirectional"))
    )
    (net (code "95") (name "unconnected-(CELLMODEM-KEYSENSE_N2-Pad31)") (class "Default")
      (node (ref "CELLMODEM") (pin "31") (pinfunction "KEYSENSE_N2_31") (pintype "bidirectional"))
    )
    (net (code "96") (name "unconnected-(CELLMODEM-KEYSENSE_N3-Pad32)") (class "Default")
      (node (ref "CELLMODEM") (pin "32") (pinfunction "KEYSENSE_N3_32") (pintype "bidirectional"))
    )
    (net (code "97") (name "unconnected-(CELLMODEM-MIC1N-Pad24)") (class "Default")
      (node (ref "CELLMODEM") (pin "24") (pinfunction "MIC1N_24") (pintype "bidirectional"))
    )
    (net (code "98") (name "unconnected-(CELLMODEM-MIC1P-Pad23)") (class "Default")
      (node (ref "CELLMODEM") (pin "23") (pinfunction "MIC1P_23") (pintype "bidirectional"))
    )
    (net (code "99") (name "unconnected-(CELLMODEM-PCM_CLK-Pad76)") (class "Default")
      (node (ref "CELLMODEM") (pin "76") (pinfunction "PCM_CLK_76") (pintype "bidirectional"))
    )
    (net (code "100") (name "unconnected-(CELLMODEM-PCM_DIN-Pad74)") (class "Default")
      (node (ref "CELLMODEM") (pin "74") (pinfunction "PCM_DIN_74") (pintype "bidirectional"))
    )
    (net (code "101") (name "unconnected-(CELLMODEM-PCM_DOUT-Pad73)") (class "Default")
      (node (ref "CELLMODEM") (pin "73") (pinfunction "PCM_DOUT_73") (pintype "bidirectional"))
    )
    (net (code "102") (name "unconnected-(CELLMODEM-PCM_SYNC-Pad75)") (class "Default")
      (node (ref "CELLMODEM") (pin "75") (pinfunction "PCM_SYNC_75") (pintype "bidirectional"))
    )
    (net (code "103") (name "unconnected-(CELLMODEM-RESERVED-Pad15)") (class "Default")
      (node (ref "CELLMODEM") (pin "15") (pinfunction "RESERVED_15") (pintype "bidirectional"))
    )
    (net (code "104") (name "unconnected-(CELLMODEM-RESERVED-Pad16)") (class "Default")
      (node (ref "CELLMODEM") (pin "16") (pinfunction "RESERVED_16") (pintype "bidirectional"))
    )
    (net (code "105") (name "unconnected-(CELLMODEM-SPI_CLK-Pad6)") (class "Default")
      (node (ref "CELLMODEM") (pin "6") (pinfunction "SPI_CLK_6") (pintype "bidirectional"))
    )
    (net (code "106") (name "unconnected-(CELLMODEM-SPI_CS_N-Pad9)") (class "Default")
      (node (ref "CELLMODEM") (pin "9") (pinfunction "SPI_CS_N_9") (pintype "bidirectional"))
    )
    (net (code "107") (name "unconnected-(CELLMODEM-SPI_MISO_DATA-Pad7)") (class "Default")
      (node (ref "CELLMODEM") (pin "7") (pinfunction "SPI_MISO_DATA_7") (pintype "bidirectional"))
    )
    (net (code "108") (name "unconnected-(CELLMODEM-SPI_MOSI_DATA-Pad8)") (class "Default")
      (node (ref "CELLMODEM") (pin "8") (pinfunction "SPI_MOSI_DATA_8") (pintype "bidirectional"))
    )
    (net (code "109") (name "unconnected-(CELLMODEM-SPK_M-Pad21)") (class "Default")
      (node (ref "CELLMODEM") (pin "21") (pinfunction "SPK_M_21") (pintype "bidirectional"))
    )
    (net (code "110") (name "unconnected-(CELLMODEM-SPK_P-Pad22)") (class "Default")
      (node (ref "CELLMODEM") (pin "22") (pinfunction "SPK_P_22") (pintype "bidirectional"))
    )
    (net (code "111") (name "unconnected-(CELLMODEM-UART_CTS-Pad67)") (class "Default")
      (node (ref "CELLMODEM") (pin "67") (pinfunction "UART_CTS_67") (pintype "bidirectional"))
    )
    (net (code "112") (name "unconnected-(CELLMODEM-UART_DCD-Pad70)") (class "Default")
      (node (ref "CELLMODEM") (pin "70") (pinfunction "UART_DCD_70") (pintype "bidirectional"))
    )
    (net (code "113") (name "unconnected-(CELLMODEM-UART_DTR-Pad72)") (class "Default")
      (node (ref "CELLMODEM") (pin "72") (pinfunction "UART_DTR_72") (pintype "bidirectional"))
    )
    (net (code "114") (name "unconnected-(CELLMODEM-UART_RTS-Pad66)") (class "Default")
      (node (ref "CELLMODEM") (pin "66") (pinfunction "UART_RTS_66") (pintype "bidirectional"))
    )
    (net (code "115") (name "unconnected-(CELLMODEM-USB_VBUS-Pad11)") (class "Default")
      (node (ref "CELLMODEM") (pin "11") (pinfunction "USB_VBUS_11") (pintype "bidirectional"))
    )
    (net (code "116") (name "unconnected-(CELLMODEM-VREG_AUX-Pad44)") (class "Default")
      (node (ref "CELLMODEM") (pin "44") (pinfunction "VREG_AUX_44") (pintype "bidirectional"))
    )
    (net (code "117") (name "unconnected-(CELLMODEM-VRTC-Pad42)") (class "Default")
      (node (ref "CELLMODEM") (pin "42") (pinfunction "VRTC_42") (pintype "bidirectional"))
    )
    (net (code "118") (name "unconnected-(J1-VPP-PadC6)") (class "Default")
      (node (ref "J1") (pin "C6") (pinfunction "VPP_C6") (pintype "input"))
    )
    (net (code "119") (name "unconnected-(JTAG-Pad4)") (class "Default")
      (node (ref "JTAG") (pin "4") (pinfunction "4_4") (pintype "passive"))
    )
    (net (code "120") (name "unconnected-(JTAG-Pad6)") (class "Default")
      (node (ref "JTAG") (pin "6") (pinfunction "6_6") (pintype "passive"))
    )
    (net (code "121") (name "unconnected-(LCD-P$1-Pad1)") (class "Default")
      (node (ref "LCD") (pin "1") (pinfunction "P$1_1") (pintype "bidirectional"))
    )
    (net (code "122") (name "unconnected-(LCD-P$2-Pad2)") (class "Default")
      (node (ref "LCD") (pin "2") (pinfunction "P$2_2") (pintype "bidirectional"))
    )
    (net (code "123") (name "unconnected-(LCD-P$9-Pad9)") (class "Default")
      (node (ref "LCD") (pin "9") (pinfunction "P$9_9") (pintype "bidirectional"))
    )
    (net (code "124") (name "unconnected-(LCD-P$10-Pad10)") (class "Default")
      (node (ref "LCD") (pin "10") (pinfunction "P$10_10") (pintype "bidirectional"))
    )
    (net (code "125") (name "unconnected-(MICROC-PadP$1)") (class "Default")
      (node (ref "MICROC") (pin "P$1") (pinfunction "P$1_P$1") (pintype "bidirectional"))
    )
    (net (code "126") (name "unconnected-(MICROC-PadP$6)") (class "Default")
      (node (ref "MICROC") (pin "P$6") (pinfunction "P$6_P$6") (pintype "bidirectional"))
    )
    (net (code "127") (name "unconnected-(MICROC-PadP$8)") (class "Default")
      (node (ref "MICROC") (pin "P$8") (pinfunction "P$8_P$8") (pintype "bidirectional"))
    )
    (net (code "128") (name "unconnected-(MICROC-PadP$9)") (class "Default")
      (node (ref "MICROC") (pin "P$9") (pinfunction "P$9_P$9") (pintype "bidirectional"))
    )
    (net (code "129") (name "unconnected-(MICROC-PadP$12)") (class "Default")
      (node (ref "MICROC") (pin "P$12") (pinfunction "P$12_P$12") (pintype "bidirectional"))
    )
    (net (code "130") (name "unconnected-(MICROC-PadP$13)") (class "Default")
      (node (ref "MICROC") (pin "P$13") (pinfunction "P$13_P$13") (pintype "bidirectional"))
    )
    (net (code "131") (name "unconnected-(MICROC-PadP$14)") (class "Default")
      (node (ref "MICROC") (pin "P$14") (pinfunction "P$14_P$14") (pintype "bidirectional"))
    )
    (net (code "132") (name "unconnected-(MICROC-PadP$15)") (class "Default")
      (node (ref "MICROC") (pin "P$15") (pinfunction "P$15_P$15") (pintype "bidirectional"))
    )
    (net (code "133") (name "unconnected-(MICROC-PadP$16)") (class "Default")
      (node (ref "MICROC") (pin "P$16") (pinfunction "P$16_P$16") (pintype "bidirectional"))
    )
    (net (code "134") (name "unconnected-(MICROC-PadP$17)") (class "Default")
      (node (ref "MICROC") (pin "P$17") (pinfunction "P$17_P$17") (pintype "bidirectional"))
    )
    (net (code "135") (name "unconnected-(MICROC-PadP$18)") (class "Default")
      (node (ref "MICROC") (pin "P$18") (pinfunction "P$18_P$18") (pintype "bidirectional"))
    )
    (net (code "136") (name "unconnected-(MICROC-PadP$19)") (class "Default")
      (node (ref "MICROC") (pin "P$19") (pinfunction "P$19_P$19") (pintype "bidirectional"))
    )
    (net (code "137") (name "unconnected-(MICROC-PadP$20)") (class "Default")
      (node (ref "MICROC") (pin "P$20") (pinfunction "P$20_P$20") (pintype "bidirectional"))
    )
    (net (code "138") (name "unconnected-(MICROC-PadP$21)") (class "Default")
      (node (ref "MICROC") (pin "P$21") (pinfunction "P$21_P$21") (pintype "bidirectional"))
    )
    (net (code "139") (name "unconnected-(MICROC-PadP$22)") (class "Default")
      (node (ref "MICROC") (pin "P$22") (pinfunction "P$22_P$22") (pintype "bidirectional"))
    )
    (net (code "140") (name "unconnected-(MICROC-PadP$23)") (class "Default")
      (node (ref "MICROC") (pin "P$23") (pinfunction "P$23_P$23") (pintype "bidirectional"))
    )
    (net (code "141") (name "unconnected-(MICROC-PadP$24)") (class "Default")
      (node (ref "MICROC") (pin "P$24") (pinfunction "P$24_P$24") (pintype "bidirectional"))
    )
    (net (code "142") (name "unconnected-(MICROC-PadP$25)") (class "Default")
      (node (ref "MICROC") (pin "P$25") (pinfunction "P$25_P$25") (pintype "bidirectional"))
    )
    (net (code "143") (name "unconnected-(MICROC-PadP$34)") (class "Default")
      (node (ref "MICROC") (pin "P$34") (pinfunction "P$34_P$34") (pintype "bidirectional"))
    )
    (net (code "144") (name "unconnected-(MICROC-PadP$35)") (class "Default")
      (node (ref "MICROC") (pin "P$35") (pinfunction "P$35_P$35") (pintype "bidirectional"))
    )
    (net (code "145") (name "unconnected-(MICROC-PadP$36)") (class "Default")
      (node (ref "MICROC") (pin "P$36") (pinfunction "P$36_P$36") (pintype "bidirectional"))
    )
    (net (code "146") (name "unconnected-(MICROC-PadP$37)") (class "Default")
      (node (ref "MICROC") (pin "P$37") (pinfunction "P$37_P$37") (pintype "bidirectional"))
    )
    (net (code "147") (name "unconnected-(MICROC-PadP$38)") (class "Default")
      (node (ref "MICROC") (pin "P$38") (pinfunction "P$38_P$38") (pintype "bidirectional"))
    )
    (net (code "148") (name "unconnected-(MICROC-PadP$44)") (class "Default")
      (node (ref "MICROC") (pin "P$44") (pinfunction "P$44_P$44") (pintype "bidirectional"))
    )
    (net (code "149") (name "unconnected-(MICROC-PadP$45)") (class "Default")
      (node (ref "MICROC") (pin "P$45") (pinfunction "P$45_P$45") (pintype "bidirectional"))
    )
    (net (code "150") (name "unconnected-(MICROC-PadP$46)") (class "Default")
      (node (ref "MICROC") (pin "P$46") (pinfunction "P$46_P$46") (pintype "bidirectional"))
    )
    (net (code "151") (name "unconnected-(MICROC-PadP$52)") (class "Default")
      (node (ref "MICROC") (pin "P$52") (pinfunction "P$52_P$52") (pintype "bidirectional"))
    )
    (net (code "152") (name "unconnected-(MICROC-PadP$53)") (class "Default")
      (node (ref "MICROC") (pin "P$53") (pinfunction "P$53_P$53") (pintype "bidirectional"))
    )
    (net (code "153") (name "unconnected-(MICROC-PadP$54)") (class "Default")
      (node (ref "MICROC") (pin "P$54") (pinfunction "P$54_P$54") (pintype "bidirectional"))
    )
    (net (code "154") (name "unconnected-(MICROC-PadP$55)") (class "Default")
      (node (ref "MICROC") (pin "P$55") (pinfunction "P$55_P$55") (pintype "bidirectional"))
    )
    (net (code "155") (name "unconnected-(MICROC-PadP$56)") (class "Default")
      (node (ref "MICROC") (pin "P$56") (pinfunction "P$56_P$56") (pintype "bidirectional"))
    )
    (net (code "156") (name "unconnected-(MICROC-PadP$59)") (class "Default")
      (node (ref "MICROC") (pin "P$59") (pinfunction "P$59_P$59") (pintype "bidirectional"))
    )
    (net (code "157") (name "unconnected-(MICROC-PadP$60)") (class "Default")
      (node (ref "MICROC") (pin "P$60") (pinfunction "P$60_P$60") (pintype "bidirectional"))
    )
    (net (code "158") (name "unconnected-(MICROC-PadP$61)") (class "Default")
      (node (ref "MICROC") (pin "P$61") (pinfunction "P$61_P$61") (pintype "bidirectional"))
    )
    (net (code "159") (name "unconnected-(MICROC-PadP$62)") (class "Default")
      (node (ref "MICROC") (pin "P$62") (pinfunction "P$62_P$62") (pintype "bidirectional"))
    )
    (net (code "160") (name "unconnected-(MICROC-PadP$63)") (class "Default")
      (node (ref "MICROC") (pin "P$63") (pinfunction "P$63_P$63") (pintype "bidirectional"))
    )
    (net (code "161") (name "unconnected-(MICROC-PadP$64)") (class "Default")
      (node (ref "MICROC") (pin "P$64") (pinfunction "P$64_P$64") (pintype "bidirectional"))
    )
    (net (code "162") (name "unconnected-(MICROC-PadP$65)") (class "Default")
      (node (ref "MICROC") (pin "P$65") (pinfunction "P$65_P$65") (pintype "bidirectional"))
    )
    (net (code "163") (name "unconnected-(MICROC-PadP$66)") (class "Default")
      (node (ref "MICROC") (pin "P$66") (pinfunction "P$66_P$66") (pintype "bidirectional"))
    )
    (net (code "164") (name "unconnected-(MICROC-PadP$67)") (class "Default")
      (node (ref "MICROC") (pin "P$67") (pinfunction "P$67_P$67") (pintype "bidirectional"))
    )
    (net (code "165") (name "unconnected-(MICROC-PadP$68)") (class "Default")
      (node (ref "MICROC") (pin "P$68") (pinfunction "P$68_P$68") (pintype "bidirectional"))
    )
    (net (code "166") (name "unconnected-(MICROC-PadP$69)") (class "Default")
      (node (ref "MICROC") (pin "P$69") (pinfunction "P$69_P$69") (pintype "bidirectional"))
    )
    (net (code "167") (name "unconnected-(MICROC-PadP$70)") (class "Default")
      (node (ref "MICROC") (pin "P$70") (pinfunction "P$70_P$70") (pintype "bidirectional"))
    )
    (net (code "168") (name "unconnected-(MICROC-PadP$71)") (class "Default")
      (node (ref "MICROC") (pin "P$71") (pinfunction "P$71_P$71") (pintype "bidirectional"))
    )
    (net (code "169") (name "unconnected-(MICROC-PadP$72)") (class "Default")
      (node (ref "MICROC") (pin "P$72") (pinfunction "P$72_P$72") (pintype "bidirectional"))
    )
    (net (code "170") (name "unconnected-(MICROC-PadP$73)") (class "Default")
      (node (ref "MICROC") (pin "P$73") (pinfunction "P$73_P$73") (pintype "bidirectional"))
    )
    (net (code "171") (name "unconnected-(MICROC-PadP$74)") (class "Default")
      (node (ref "MICROC") (pin "P$74") (pinfunction "P$74_P$74") (pintype "bidirectional"))
    )
    (net (code "172") (name "unconnected-(MICROC-PadP$77)") (class "Default")
      (node (ref "MICROC") (pin "P$77") (pinfunction "P$77_P$77") (pintype "bidirectional"))
    )
    (net (code "173") (name "unconnected-(MICROC-PadP$78)") (class "Default")
      (node (ref "MICROC") (pin "P$78") (pinfunction "P$78_P$78") (pintype "bidirectional"))
    )
    (net (code "174") (name "unconnected-(MICROC-PadP$81)") (class "Default")
      (node (ref "MICROC") (pin "P$81") (pinfunction "P$81_P$81") (pintype "bidirectional"))
    )
    (net (code "175") (name "unconnected-(MICROC-PadP$87)") (class "Default")
      (node (ref "MICROC") (pin "P$87") (pinfunction "P$87_P$87") (pintype "bidirectional"))
    )
    (net (code "176") (name "unconnected-(MICROC-PadP$88)") (class "Default")
      (node (ref "MICROC") (pin "P$88") (pinfunction "P$88_P$88") (pintype "bidirectional"))
    )
    (net (code "177") (name "unconnected-(MICROC-PadP$89)") (class "Default")
      (node (ref "MICROC") (pin "P$89") (pinfunction "P$89_P$89") (pintype "bidirectional"))
    )
    (net (code "178") (name "unconnected-(MICROC-PadP$91)") (class "Default")
      (node (ref "MICROC") (pin "P$91") (pinfunction "P$91_P$91") (pintype "bidirectional"))
    )
    (net (code "179") (name "unconnected-(MICROC-PadP$95)") (class "Default")
      (node (ref "MICROC") (pin "P$95") (pinfunction "P$95_P$95") (pintype "bidirectional"))
    )
    (net (code "180") (name "unconnected-(MICROC-PadP$96)") (class "Default")
      (node (ref "MICROC") (pin "P$96") (pinfunction "P$96_P$96") (pintype "bidirectional"))
    )
    (net (code "181") (name "unconnected-(MICROC-PadP$97)") (class "Default")
      (node (ref "MICROC") (pin "P$97") (pinfunction "P$97_P$97") (pintype "bidirectional"))
    )
    (net (code "182") (name "unconnected-(MICROC-PadP$100)") (class "Default")
      (node (ref "MICROC") (pin "P$100") (pinfunction "P$100_P$100") (pintype "bidirectional"))
    )
    (net (code "183") (name "unconnected-(MICROUSB-PadID)") (class "Default")
      (node (ref "MICROUSB") (pin "ID") (pinfunction "ID_ID") (pintype "bidirectional"))
    )
    (net (code "184") (name "unconnected-(SMF05C-C5-Pad6)") (class "Default")
      (node (ref "SMF05C") (pin "6") (pinfunction "C5_6") (pintype "passive"))
    )
  )
)
